# VGABoard.net
KiCad netlist of a schematic drawn in EAGLE
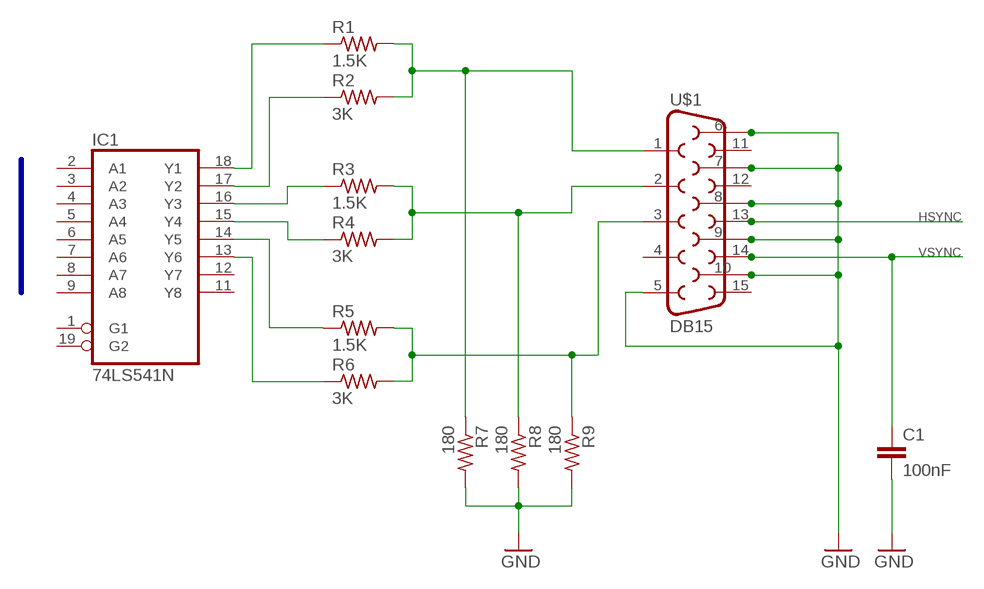
[diagram p0: schematic, sheet 1]

(export (version "E")
  (design (tool "Eeschema 10.0.6"))
  (components
    (comp (ref "C1")
      (value "100nF")
      (footprint "eagle-import:CAP-PTH-SMALLEZ")
      (libsource (lib "eagle-import") (part "CAPEZ"))
    )
    (comp (ref "IC1")
      (value "74LS541N")
      (footprint "eagle-import:DIL20")
      (libsource (lib "eagle-import") (part "74541NLS"))
    )
    (comp (ref "R1")
      (value "1.5K")
      (footprint "eagle-import:0204_5")
      (libsource (lib "eagle-import") (part "R-US_0204/5"))
    )
    (comp (ref "R2")
      (value "3K")
      (footprint "eagle-import:0204_5")
      (libsource (lib "eagle-import") (part "R-US_0204/5"))
    )
    (comp (ref "R3")
      (value "1.5K")
      (footprint "eagle-import:0204_5")
      (libsource (lib "eagle-import") (part "R-US_0204/5"))
    )
    (comp (ref "R4")
      (value "3K")
      (footprint "eagle-import:0204_5")
      (libsource (lib "eagle-import") (part "R-US_0204/5"))
    )
    (comp (ref "R5")
      (value "1.5K")
      (footprint "eagle-import:0204_5")
      (libsource (lib "eagle-import") (part "R-US_0204/5"))
    )
    (comp (ref "R6")
      (value "3K")
      (footprint "eagle-import:0204_5")
      (libsource (lib "eagle-import") (part "R-US_0204/5"))
    )
    (comp (ref "R7")
      (value "180")
      (footprint "eagle-import:0204_5")
      (libsource (lib "eagle-import") (part "R-US_0204/5"))
    )
    (comp (ref "R8")
      (value "180")
      (footprint "eagle-import:0204_5")
      (libsource (lib "eagle-import") (part "R-US_0204/5"))
    )
    (comp (ref "R9")
      (value "180")
      (footprint "eagle-import:0204_5")
      (libsource (lib "eagle-import") (part "R-US_0204/5"))
    )
    (comp (ref "U$1")
      (value "DB15")
      (footprint "eagle-import:DB15")
      (libsource (lib "eagle-import") (part "DB15"))
    )
  )
  (nets
    (net (code "1") (name "/HSYNC") (class "Default")
      (node (ref "U$1") (pin "13") (pinfunction "13_13") (pintype "passive"))
    )
    (net (code "2") (name "/VSYNC") (class "Default")
      (node (ref "C1") (pin "1") (pinfunction "1_1") (pintype "passive"))
      (node (ref "U$1") (pin "14") (pinfunction "14_14") (pintype "passive"))
    )
    (net (code "3") (name "GND") (class "Default")
      (node (ref "C1") (pin "2") (pinfunction "2_2") (pintype "passive"))
      (node (ref "R7") (pin "2") (pinfunction "2_2") (pintype "passive"))
      (node (ref "R8") (pin "2") (pinfunction "2_2") (pintype "passive"))
      (node (ref "R9") (pin "2") (pinfunction "2_2") (pintype "passive"))
      (node (ref "U$1") (pin "10") (pinfunction "10_10") (pintype "passive"))
      (node (ref "U$1") (pin "5") (pinfunction "5_5") (pintype "passive"))
      (node (ref "U$1") (pin "6") (pinfunction "6_6") (pintype "passive"))
      (node (ref "U$1") (pin "7") (pinfunction "7_7") (pintype "passive"))
      (node (ref "U$1") (pin "8") (pinfunction "8_8") (pintype "passive"))
      (node (ref "U$1") (pin "9") (pinfunction "9_9") (pintype "passive"))
    )
    (net (code "4") (name "Net-(IC1A-Y1)") (class "Default")
      (node (ref "IC1") (pin "18") (pinfunction "Y1_18") (pintype "tri_state"))
      (node (ref "R1") (pin "1") (pinfunction "1_1") (pintype "passive"))
    )
    (net (code "5") (name "Net-(IC1A-Y2)") (class "Default")
      (node (ref "IC1") (pin "17") (pinfunction "Y2_17") (pintype "tri_state"))
      (node (ref "R2") (pin "1") (pinfunction "1_1") (pintype "passive"))
    )
    (net (code "6") (name "Net-(IC1A-Y3)") (class "Default")
      (node (ref "IC1") (pin "16") (pinfunction "Y3_16") (pintype "tri_state"))
      (node (ref "R3") (pin "1") (pinfunction "1_1") (pintype "passive"))
    )
    (net (code "7") (name "Net-(IC1A-Y4)") (class "Default")
      (node (ref "IC1") (pin "15") (pinfunction "Y4_15") (pintype "tri_state"))
      (node (ref "R4") (pin "1") (pinfunction "1_1") (pintype "passive"))
    )
    (net (code "8") (name "Net-(IC1A-Y5)") (class "Default")
      (node (ref "IC1") (pin "14") (pinfunction "Y5_14") (pintype "tri_state"))
      (node (ref "R5") (pin "1") (pinfunction "1_1") (pintype "passive"))
    )
    (net (code "9") (name "Net-(IC1A-Y6)") (class "Default")
      (node (ref "IC1") (pin "13") (pinfunction "Y6_13") (pintype "tri_state"))
      (node (ref "R6") (pin "1") (pinfunction "1_1") (pintype "passive"))
    )
    (net (code "10") (name "Net-(R1-Pad2)") (class "Default")
      (node (ref "R1") (pin "2") (pinfunction "2_2") (pintype "passive"))
      (node (ref "R2") (pin "2") (pinfunction "2_2") (pintype "passive"))
      (node (ref "R7") (pin "1") (pinfunction "1_1") (pintype "passive"))
      (node (ref "U$1") (pin "1") (pinfunction "1_1") (pintype "passive"))
    )
    (net (code "11") (name "Net-(R3-Pad2)") (class "Default")
      (node (ref "R3") (pin "2") (pinfunction "2_2") (pintype "passive"))
      (node (ref "R4") (pin "2") (pinfunction "2_2") (pintype "passive"))
      (node (ref "R8") (pin "1") (pinfunction "1_1") (pintype "passive"))
      (node (ref "U$1") (pin "2") (pinfunction "2_2") (pintype "passive"))
    )
    (net (code "12") (name "Net-(R5-Pad2)") (class "Default")
      (node (ref "R5") (pin "2") (pinfunction "2_2") (pintype "passive"))
      (node (ref "R6") (pin "2") (pinfunction "2_2") (pintype "passive"))
      (node (ref "R9") (pin "1") (pinfunction "1_1") (pintype "passive"))
      (node (ref "U$1") (pin "3") (pinfunction "3_3") (pintype "passive"))
    )
    (net (code "13") (name "unconnected-(IC1A-A1-Pad2)") (class "Default")
      (node (ref "IC1") (pin "2") (pinfunction "A1_2") (pintype "input"))
    )
    (net (code "14") (name "unconnected-(IC1A-A2-Pad3)") (class "Default")
      (node (ref "IC1") (pin "3") (pinfunction "A2_3") (pintype "input"))
    )
    (net (code "15") (name "unconnected-(IC1A-A3-Pad4)") (class "Default")
      (node (ref "IC1") (pin "4") (pinfunction "A3_4") (pintype "input"))
    )
    (net (code "16") (name "unconnected-(IC1A-A4-Pad5)") (class "Default")
      (node (ref "IC1") (pin "5") (pinfunction "A4_5") (pintype "input"))
    )
    (net (code "17") (name "unconnected-(IC1A-A5-Pad6)") (class "Default")
      (node (ref "IC1") (pin "6") (pinfunction "A5_6") (pintype "input"))
    )
    (net (code "18") (name "unconnected-(IC1A-A6-Pad7)") (class "Default")
      (node (ref "IC1") (pin "7") (pinfunction "A6_7") (pintype "input"))
    )
    (net (code "19") (name "unconnected-(IC1A-A7-Pad8)") (class "Default")
      (node (ref "IC1") (pin "8") (pinfunction "A7_8") (pintype "input"))
    )
    (net (code "20") (name "unconnected-(IC1A-A8-Pad9)") (class "Default")
      (node (ref "IC1") (pin "9") (pinfunction "A8_9") (pintype "input"))
    )
    (net (code "21") (name "unconnected-(IC1A-G1-Pad1)") (class "Default")
      (node (ref "IC1") (pin "1") (pinfunction "G1_1") (pintype "input"))
    )
    (net (code "22") (name "unconnected-(IC1A-G2-Pad19)") (class "Default")
      (node (ref "IC1") (pin "19") (pinfunction "G2_19") (pintype "input"))
    )
    (net (code "23") (name "unconnected-(IC1A-Y7-Pad12)") (class "Default")
      (node (ref "IC1") (pin "12") (pinfunction "Y7_12") (pintype "tri_state"))
    )
    (net (code "24") (name "unconnected-(IC1A-Y8-Pad11)") (class "Default")
      (node (ref "IC1") (pin "11") (pinfunction "Y8_11") (pintype "tri_state"))
    )
    (net (code "25") (name "unconnected-(U$1-Pad4)") (class "Default")
      (node (ref "U$1") (pin "4") (pinfunction "4_4") (pintype "passive"))
    )
    (net (code "26") (name "unconnected-(U$1-Pad11)") (class "Default")
      (node (ref "U$1") (pin "11") (pinfunction "11_11") (pintype "passive"))
    )
    (net (code "27") (name "unconnected-(U$1-Pad12)") (class "Default")
      (node (ref "U$1") (pin "12") (pinfunction "12_12") (pintype "passive"))
    )
    (net (code "28") (name "unconnected-(U$1-Pad15)") (class "Default")
      (node (ref "U$1") (pin "15") (pinfunction "15_15") (pintype "passive"))
    )
  )
)
